# W640D.net
KiCad netlist of a schematic drawn in EAGLE
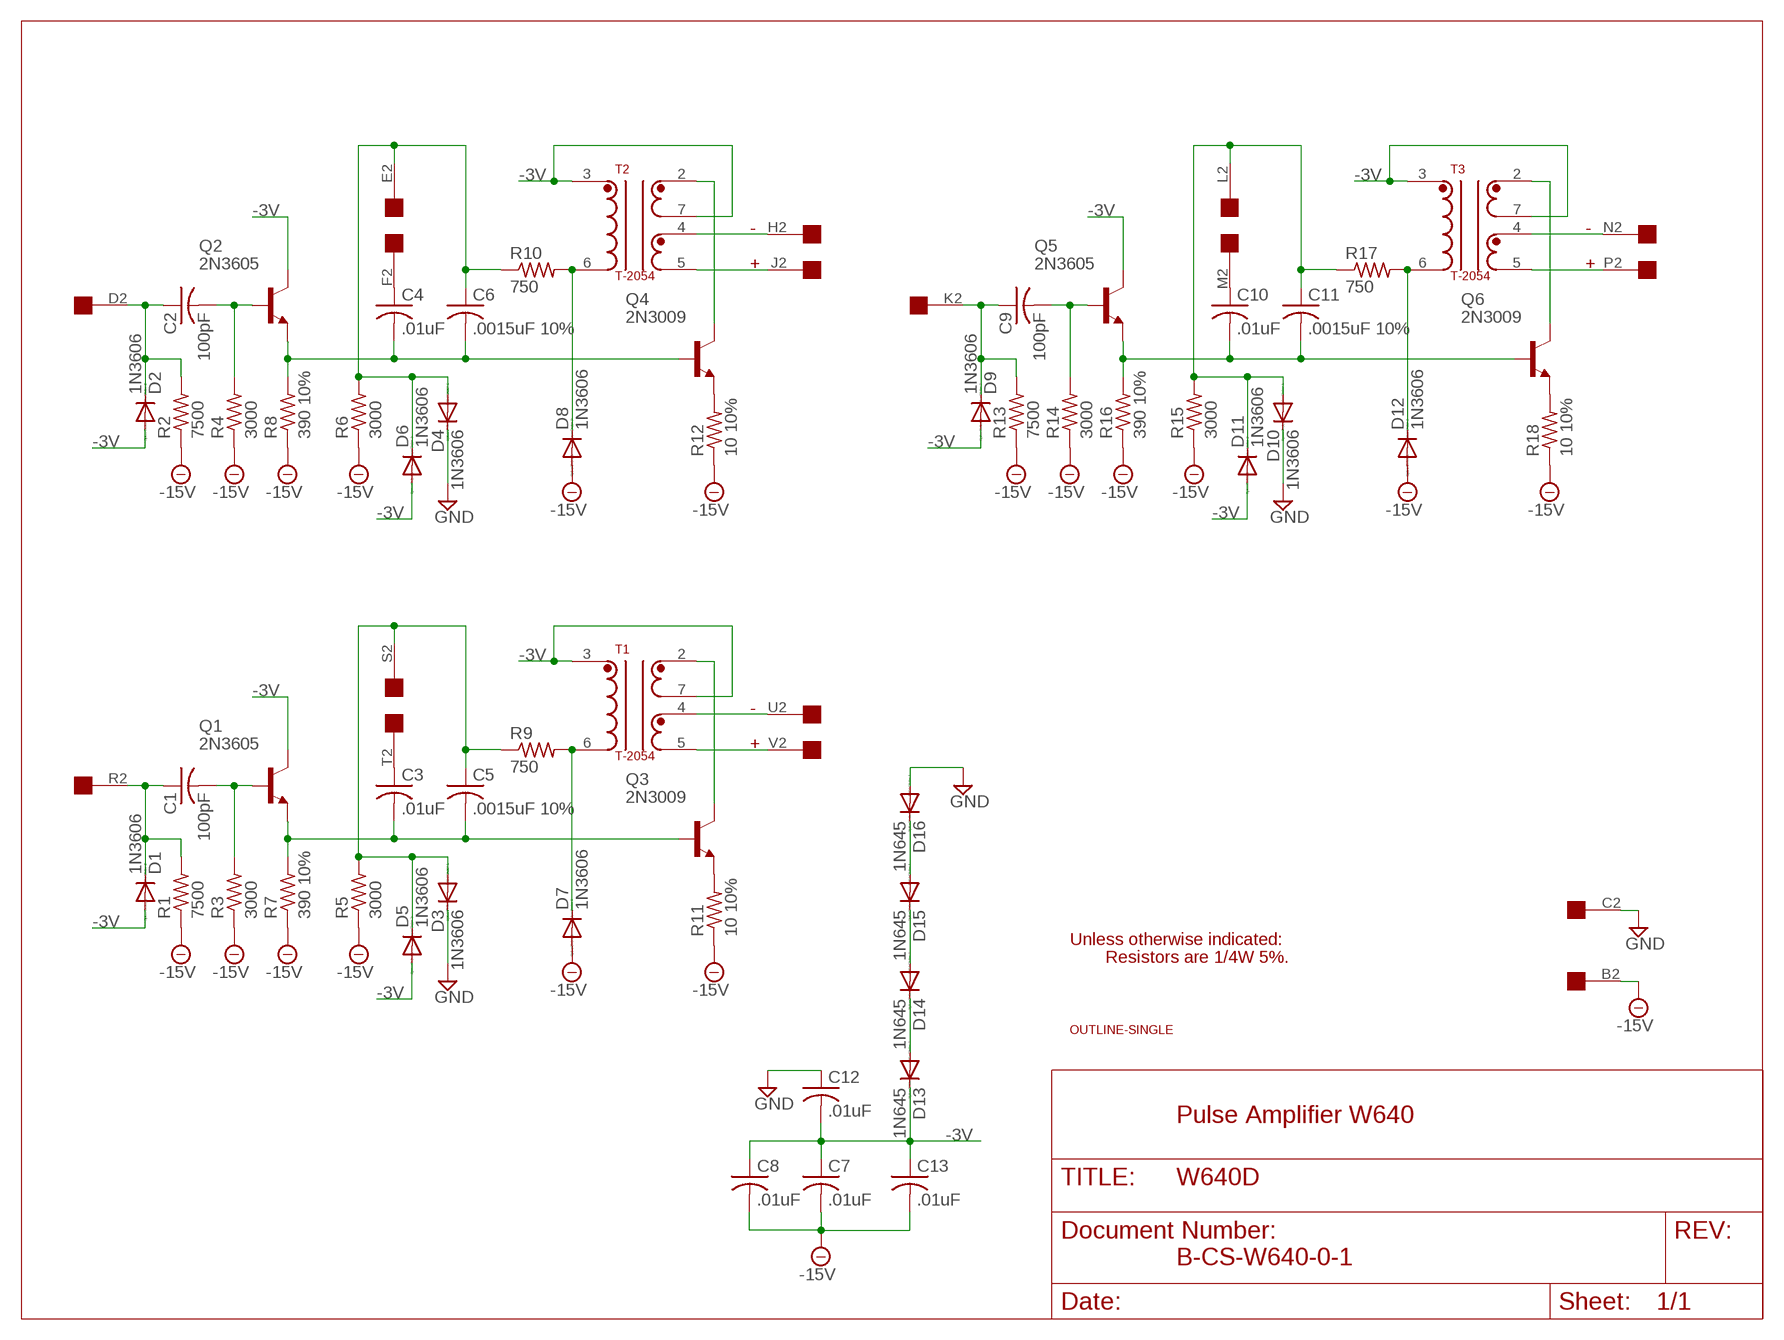
[diagram p0: schematic, sheet 1]

(export (version "E")
  (design (tool "Eeschema 10.0.6"))
  (components
    (comp (ref "C1")
      (value "100pF")
      (footprint "eagle-import:C050-025X075")
      (libsource (lib "eagle-import") (part "C-US050-025X075"))
    )
    (comp (ref "C2")
      (value "100pF")
      (footprint "eagle-import:C050-025X075")
      (libsource (lib "eagle-import") (part "C-US050-025X075"))
    )
    (comp (ref "C3")
      (value ".01uF")
      (footprint "eagle-import:C050-025X075")
      (libsource (lib "eagle-import") (part "C-US050-025X075"))
    )
    (comp (ref "C4")
      (value ".01uF")
      (footprint "eagle-import:C050-025X075")
      (libsource (lib "eagle-import") (part "C-US050-025X075"))
    )
    (comp (ref "C5")
      (value ".0015uF 10%")
      (footprint "eagle-import:C050-025X075")
      (libsource (lib "eagle-import") (part "C-US050-025X075"))
    )
    (comp (ref "C6")
      (value ".0015uF 10%")
      (footprint "eagle-import:C050-025X075")
      (libsource (lib "eagle-import") (part "C-US050-025X075"))
    )
    (comp (ref "C7")
      (value ".01uF")
      (footprint "eagle-import:C050-025X075")
      (libsource (lib "eagle-import") (part "C-US050-025X075"))
    )
    (comp (ref "C8")
      (value ".01uF")
      (footprint "eagle-import:C050-025X075")
      (libsource (lib "eagle-import") (part "C-US050-025X075"))
    )
    (comp (ref "C9")
      (value "100pF")
      (footprint "eagle-import:C050-025X075")
      (libsource (lib "eagle-import") (part "C-US050-025X075"))
    )
    (comp (ref "C10")
      (value ".01uF")
      (footprint "eagle-import:C050-025X075")
      (libsource (lib "eagle-import") (part "C-US050-025X075"))
    )
    (comp (ref "C11")
      (value ".0015uF 10%")
      (footprint "eagle-import:C050-025X075")
      (libsource (lib "eagle-import") (part "C-US050-025X075"))
    )
    (comp (ref "C12")
      (value ".01uF")
      (footprint "eagle-import:C050-025X075")
      (libsource (lib "eagle-import") (part "C-US050-025X075"))
    )
    (comp (ref "C13")
      (value ".01uF")
      (footprint "eagle-import:C050-025X075")
      (libsource (lib "eagle-import") (part "C-US050-025X075"))
    )
    (comp (ref "D1")
      (value "1N3606")
      (footprint "eagle-import:DO35-10")
      (libsource (lib "eagle-import") (part "1N4148DO35-10"))
    )
    (comp (ref "D2")
      (value "1N3606")
      (footprint "eagle-import:DO35-10")
      (libsource (lib "eagle-import") (part "1N4148DO35-10"))
    )
    (comp (ref "D3")
      (value "1N3606")
      (footprint "eagle-import:DO35-10")
      (libsource (lib "eagle-import") (part "1N4148DO35-10"))
    )
    (comp (ref "D4")
      (value "1N3606")
      (footprint "eagle-import:DO35-10")
      (libsource (lib "eagle-import") (part "1N4148DO35-10"))
    )
    (comp (ref "D5")
      (value "1N3606")
      (footprint "eagle-import:DO35-10")
      (libsource (lib "eagle-import") (part "1N4148DO35-10"))
    )
    (comp (ref "D6")
      (value "1N3606")
      (footprint "eagle-import:DO35-10")
      (libsource (lib "eagle-import") (part "1N4148DO35-10"))
    )
    (comp (ref "D7")
      (value "1N3606")
      (footprint "eagle-import:DO35-10")
      (libsource (lib "eagle-import") (part "1N4148DO35-10"))
    )
    (comp (ref "D8")
      (value "1N3606")
      (footprint "eagle-import:DO35-10")
      (libsource (lib "eagle-import") (part "1N4148DO35-10"))
    )
    (comp (ref "D9")
      (value "1N3606")
      (footprint "eagle-import:DO35-10")
      (libsource (lib "eagle-import") (part "1N4148DO35-10"))
    )
    (comp (ref "D10")
      (value "1N3606")
      (footprint "eagle-import:DO35-10")
      (libsource (lib "eagle-import") (part "1N4148DO35-10"))
    )
    (comp (ref "D11")
      (value "1N3606")
      (footprint "eagle-import:DO35-10")
      (libsource (lib "eagle-import") (part "1N4148DO35-10"))
    )
    (comp (ref "D12")
      (value "1N3606")
      (footprint "eagle-import:DO35-10")
      (libsource (lib "eagle-import") (part "1N4148DO35-10"))
    )
    (comp (ref "D13")
      (value "1N645")
      (footprint "eagle-import:DO35-10")
      (libsource (lib "eagle-import") (part "1N4148DO35-10"))
    )
    (comp (ref "D14")
      (value "1N645")
      (footprint "eagle-import:DO35-10")
      (libsource (lib "eagle-import") (part "1N4148DO35-10"))
    )
    (comp (ref "D15")
      (value "1N645")
      (footprint "eagle-import:DO35-10")
      (libsource (lib "eagle-import") (part "1N4148DO35-10"))
    )
    (comp (ref "D16")
      (value "1N645")
      (footprint "eagle-import:DO35-10")
      (libsource (lib "eagle-import") (part "1N4148DO35-10"))
    )
    (comp (ref "Q1")
      (value "2N3605")
      (footprint "eagle-import:TO5")
      (libsource (lib "eagle-import") (part "2N2219"))
    )
    (comp (ref "Q2")
      (value "2N3605")
      (footprint "eagle-import:TO5")
      (libsource (lib "eagle-import") (part "2N2219"))
    )
    (comp (ref "Q3")
      (value "2N3009")
      (footprint "eagle-import:TO5")
      (libsource (lib "eagle-import") (part "2N2219"))
    )
    (comp (ref "Q4")
      (value "2N3009")
      (footprint "eagle-import:TO5")
      (libsource (lib "eagle-import") (part "2N2219"))
    )
    (comp (ref "Q5")
      (value "2N3605")
      (footprint "eagle-import:TO5")
      (libsource (lib "eagle-import") (part "2N2219"))
    )
    (comp (ref "Q6")
      (value "2N3009")
      (footprint "eagle-import:TO5")
      (libsource (lib "eagle-import") (part "2N2219"))
    )
    (comp (ref "R1")
      (value "7500")
      (footprint "eagle-import:0207_10")
      (libsource (lib "eagle-import") (part "R-US_0207/10"))
    )
    (comp (ref "R2")
      (value "7500")
      (footprint "eagle-import:0207_10")
      (libsource (lib "eagle-import") (part "R-US_0207/10"))
    )
    (comp (ref "R3")
      (value "3000")
      (footprint "eagle-import:0207_10")
      (libsource (lib "eagle-import") (part "R-US_0207/10"))
    )
    (comp (ref "R4")
      (value "3000")
      (footprint "eagle-import:0207_10")
      (libsource (lib "eagle-import") (part "R-US_0207/10"))
    )
    (comp (ref "R5")
      (value "3000")
      (footprint "eagle-import:0207_10")
      (libsource (lib "eagle-import") (part "R-US_0207/10"))
    )
    (comp (ref "R6")
      (value "3000")
      (footprint "eagle-import:0207_10")
      (libsource (lib "eagle-import") (part "R-US_0207/10"))
    )
    (comp (ref "R7")
      (value "390 10%")
      (footprint "eagle-import:0207_10")
      (libsource (lib "eagle-import") (part "R-US_0207/10"))
    )
    (comp (ref "R8")
      (value "390 10%")
      (footprint "eagle-import:0207_10")
      (libsource (lib "eagle-import") (part "R-US_0207/10"))
    )
    (comp (ref "R9")
      (value "750")
      (footprint "eagle-import:0207_10")
      (libsource (lib "eagle-import") (part "R-US_0207/10"))
    )
    (comp (ref "R10")
      (value "750")
      (footprint "eagle-import:0207_10")
      (libsource (lib "eagle-import") (part "R-US_0207/10"))
    )
    (comp (ref "R11")
      (value "10 10%")
      (footprint "eagle-import:0207_10")
      (libsource (lib "eagle-import") (part "R-US_0207/10"))
    )
    (comp (ref "R12")
      (value "10 10%")
      (footprint "eagle-import:0207_10")
      (libsource (lib "eagle-import") (part "R-US_0207/10"))
    )
    (comp (ref "R13")
      (value "7500")
      (footprint "eagle-import:0207_10")
      (libsource (lib "eagle-import") (part "R-US_0207/10"))
    )
    (comp (ref "R14")
      (value "3000")
      (footprint "eagle-import:0207_10")
      (libsource (lib "eagle-import") (part "R-US_0207/10"))
    )
    (comp (ref "R15")
      (value "3000")
      (footprint "eagle-import:0207_10")
      (libsource (lib "eagle-import") (part "R-US_0207/10"))
    )
    (comp (ref "R16")
      (value "390 10%")
      (footprint "eagle-import:0207_10")
      (libsource (lib "eagle-import") (part "R-US_0207/10"))
    )
    (comp (ref "R17")
      (value "750")
      (footprint "eagle-import:0207_10")
      (libsource (lib "eagle-import") (part "R-US_0207/10"))
    )
    (comp (ref "R18")
      (value "10 10%")
      (footprint "eagle-import:0207_10")
      (libsource (lib "eagle-import") (part "R-US_0207/10"))
    )
    (comp (ref "T1")
      (value "T-2054")
      (footprint "eagle-import:TRANSFORMER6B")
      (libsource (lib "eagle-import") (part "T-2054"))
    )
    (comp (ref "T2")
      (value "T-2054")
      (footprint "eagle-import:TRANSFORMER6B")
      (libsource (lib "eagle-import") (part "T-2054"))
    )
    (comp (ref "T3")
      (value "T-2054")
      (footprint "eagle-import:TRANSFORMER6B")
      (libsource (lib "eagle-import") (part "T-2054"))
    )
    (comp (ref "U$1")
      (value "OUTLINE-SINGLE")
      (footprint "eagle-import:SINGLE")
      (libsource (lib "eagle-import") (part "OUTLINE-SINGLE"))
    )
    (comp (ref "U$2")
      (value "EDGE-1")
      (footprint "eagle-import:EDGE-CON1")
      (libsource (lib "eagle-import") (part "EDGE-1"))
    )
  )
  (nets
    (net (code "1") (name "-15V") (class "Default")
      (node (ref "C13") (pin "2") (pinfunction "2_2") (pintype "passive"))
      (node (ref "C7") (pin "2") (pinfunction "2_2") (pintype "passive"))
      (node (ref "C8") (pin "2") (pinfunction "2_2") (pintype "passive"))
      (node (ref "D12") (pin "A") (pinfunction "A_A") (pintype "passive"))
      (node (ref "D7") (pin "A") (pinfunction "A_A") (pintype "passive"))
      (node (ref "D8") (pin "A") (pinfunction "A_A") (pintype "passive"))
      (node (ref "R1") (pin "1") (pinfunction "1_1") (pintype "passive"))
      (node (ref "R11") (pin "1") (pinfunction "1_1") (pintype "passive"))
      (node (ref "R12") (pin "1") (pinfunction "1_1") (pintype "passive"))
      (node (ref "R13") (pin "1") (pinfunction "1_1") (pintype "passive"))
      (node (ref "R14") (pin "1") (pinfunction "1_1") (pintype "passive"))
      (node (ref "R15") (pin "1") (pinfunction "1_1") (pintype "passive"))
      (node (ref "R16") (pin "1") (pinfunction "1_1") (pintype "passive"))
      (node (ref "R18") (pin "1") (pinfunction "1_1") (pintype "passive"))
      (node (ref "R2") (pin "1") (pinfunction "1_1") (pintype "passive"))
      (node (ref "R3") (pin "1") (pinfunction "1_1") (pintype "passive"))
      (node (ref "R4") (pin "1") (pinfunction "1_1") (pintype "passive"))
      (node (ref "R5") (pin "1") (pinfunction "1_1") (pintype "passive"))
      (node (ref "R6") (pin "1") (pinfunction "1_1") (pintype "passive"))
      (node (ref "R7") (pin "1") (pinfunction "1_1") (pintype "passive"))
      (node (ref "R8") (pin "1") (pinfunction "1_1") (pintype "passive"))
      (node (ref "U$2") (pin "B2") (pinfunction "1_B2") (pintype "bidirectional"))
    )
    (net (code "2") (name "/-3V") (class "Default")
      (node (ref "C12") (pin "2") (pinfunction "2_2") (pintype "passive"))
      (node (ref "C13") (pin "1") (pinfunction "1_1") (pintype "passive"))
      (node (ref "C7") (pin "1") (pinfunction "1_1") (pintype "passive"))
      (node (ref "C8") (pin "1") (pinfunction "1_1") (pintype "passive"))
      (node (ref "D1") (pin "A") (pinfunction "A_A") (pintype "passive"))
      (node (ref "D11") (pin "A") (pinfunction "A_A") (pintype "passive"))
      (node (ref "D13") (pin "C") (pinfunction "C_C") (pintype "passive"))
      (node (ref "D2") (pin "A") (pinfunction "A_A") (pintype "passive"))
      (node (ref "D5") (pin "A") (pinfunction "A_A") (pintype "passive"))
      (node (ref "D6") (pin "A") (pinfunction "A_A") (pintype "passive"))
      (node (ref "D9") (pin "A") (pinfunction "A_A") (pintype "passive"))
      (node (ref "Q1") (pin "3") (pinfunction "C_3") (pintype "passive"))
      (node (ref "Q2") (pin "3") (pinfunction "C_3") (pintype "passive"))
      (node (ref "Q5") (pin "3") (pinfunction "C_3") (pintype "passive"))
      (node (ref "T1") (pin "3") (pinfunction "3_3") (pintype "passive"))
      (node (ref "T1") (pin "7") (pinfunction "5_7") (pintype "passive"))
      (node (ref "T2") (pin "3") (pinfunction "3_3") (pintype "passive"))
      (node (ref "T2") (pin "7") (pinfunction "5_7") (pintype "passive"))
      (node (ref "T3") (pin "3") (pinfunction "3_3") (pintype "passive"))
      (node (ref "T3") (pin "7") (pinfunction "5_7") (pintype "passive"))
    )
    (net (code "3") (name "GND") (class "Default")
      (node (ref "C12") (pin "1") (pinfunction "1_1") (pintype "passive"))
      (node (ref "D10") (pin "C") (pinfunction "C_C") (pintype "passive"))
      (node (ref "D16") (pin "A") (pinfunction "A_A") (pintype "passive"))
      (node (ref "D3") (pin "C") (pinfunction "C_C") (pintype "passive"))
      (node (ref "D4") (pin "C") (pinfunction "C_C") (pintype "passive"))
      (node (ref "U$2") (pin "C2") (pinfunction "1_C2") (pintype "bidirectional"))
    )
    (net (code "4") (name "Net-(D13-PadA)") (class "Default")
      (node (ref "D13") (pin "A") (pinfunction "A_A") (pintype "passive"))
      (node (ref "D14") (pin "C") (pinfunction "C_C") (pintype "passive"))
    )
    (net (code "5") (name "Net-(D14-PadA)") (class "Default")
      (node (ref "D14") (pin "A") (pinfunction "A_A") (pintype "passive"))
      (node (ref "D15") (pin "C") (pinfunction "C_C") (pintype "passive"))
    )
    (net (code "6") (name "Net-(D15-PadA)") (class "Default")
      (node (ref "D15") (pin "A") (pinfunction "A_A") (pintype "passive"))
      (node (ref "D16") (pin "C") (pinfunction "C_C") (pintype "passive"))
    )
    (net (code "7") (name "Net-(Q1-B)") (class "Default")
      (node (ref "C1") (pin "2") (pinfunction "2_2") (pintype "passive"))
      (node (ref "Q1") (pin "2") (pinfunction "B_2") (pintype "passive"))
      (node (ref "R3") (pin "2") (pinfunction "2_2") (pintype "passive"))
    )
    (net (code "8") (name "Net-(Q1-E)") (class "Default")
      (node (ref "C3") (pin "2") (pinfunction "2_2") (pintype "passive"))
      (node (ref "C5") (pin "2") (pinfunction "2_2") (pintype "passive"))
      (node (ref "Q1") (pin "1") (pinfunction "E_1") (pintype "passive"))
      (node (ref "Q3") (pin "2") (pinfunction "B_2") (pintype "passive"))
      (node (ref "R7") (pin "2") (pinfunction "2_2") (pintype "passive"))
    )
    (net (code "9") (name "Net-(Q2-B)") (class "Default")
      (node (ref "C2") (pin "2") (pinfunction "2_2") (pintype "passive"))
      (node (ref "Q2") (pin "2") (pinfunction "B_2") (pintype "passive"))
      (node (ref "R4") (pin "2") (pinfunction "2_2") (pintype "passive"))
    )
    (net (code "10") (name "Net-(Q2-E)") (class "Default")
      (node (ref "C4") (pin "2") (pinfunction "2_2") (pintype "passive"))
      (node (ref "C6") (pin "2") (pinfunction "2_2") (pintype "passive"))
      (node (ref "Q2") (pin "1") (pinfunction "E_1") (pintype "passive"))
      (node (ref "Q4") (pin "2") (pinfunction "B_2") (pintype "passive"))
      (node (ref "R8") (pin "2") (pinfunction "2_2") (pintype "passive"))
    )
    (net (code "11") (name "Net-(Q3-C)") (class "Default")
      (node (ref "Q3") (pin "3") (pinfunction "C_3") (pintype "passive"))
      (node (ref "T1") (pin "2") (pinfunction "2_2") (pintype "passive"))
    )
    (net (code "12") (name "Net-(Q3-E)") (class "Default")
      (node (ref "Q3") (pin "1") (pinfunction "E_1") (pintype "passive"))
      (node (ref "R11") (pin "2") (pinfunction "2_2") (pintype "passive"))
    )
    (net (code "13") (name "Net-(Q4-C)") (class "Default")
      (node (ref "Q4") (pin "3") (pinfunction "C_3") (pintype "passive"))
      (node (ref "T2") (pin "2") (pinfunction "2_2") (pintype "passive"))
    )
    (net (code "14") (name "Net-(Q4-E)") (class "Default")
      (node (ref "Q4") (pin "1") (pinfunction "E_1") (pintype "passive"))
      (node (ref "R12") (pin "2") (pinfunction "2_2") (pintype "passive"))
    )
    (net (code "15") (name "Net-(Q5-B)") (class "Default")
      (node (ref "C9") (pin "2") (pinfunction "2_2") (pintype "passive"))
      (node (ref "Q5") (pin "2") (pinfunction "B_2") (pintype "passive"))
      (node (ref "R14") (pin "2") (pinfunction "2_2") (pintype "passive"))
    )
    (net (code "16") (name "Net-(Q5-E)") (class "Default")
      (node (ref "C10") (pin "2") (pinfunction "2_2") (pintype "passive"))
      (node (ref "C11") (pin "2") (pinfunction "2_2") (pintype "passive"))
      (node (ref "Q5") (pin "1") (pinfunction "E_1") (pintype "passive"))
      (node (ref "Q6") (pin "2") (pinfunction "B_2") (pintype "passive"))
      (node (ref "R16") (pin "2") (pinfunction "2_2") (pintype "passive"))
    )
    (net (code "17") (name "Net-(Q6-C)") (class "Default")
      (node (ref "Q6") (pin "3") (pinfunction "C_3") (pintype "passive"))
      (node (ref "T3") (pin "2") (pinfunction "2_2") (pintype "passive"))
    )
    (net (code "18") (name "Net-(Q6-E)") (class "Default")
      (node (ref "Q6") (pin "1") (pinfunction "E_1") (pintype "passive"))
      (node (ref "R18") (pin "2") (pinfunction "2_2") (pintype "passive"))
    )
    (net (code "19") (name "Net-(T1-1)") (class "Default")
      (node (ref "T1") (pin "4") (pinfunction "1_4") (pintype "passive"))
      (node (ref "U$2") (pin "U2") (pinfunction "1_U2") (pintype "bidirectional"))
    )
    (net (code "20") (name "Net-(T1-4)") (class "Default")
      (node (ref "D7") (pin "C") (pinfunction "C_C") (pintype "passive"))
      (node (ref "R9") (pin "2") (pinfunction "2_2") (pintype "passive"))
      (node (ref "T1") (pin "6") (pinfunction "4_6") (pintype "passive"))
    )
    (net (code "21") (name "Net-(T1-6)") (class "Default")
      (node (ref "T1") (pin "5") (pinfunction "6_5") (pintype "passive"))
      (node (ref "U$2") (pin "V2") (pinfunction "1_V2") (pintype "bidirectional"))
    )
    (net (code "22") (name "Net-(T2-1)") (class "Default")
      (node (ref "T2") (pin "4") (pinfunction "1_4") (pintype "passive"))
      (node (ref "U$2") (pin "H2") (pinfunction "1_H2") (pintype "bidirectional"))
    )
    (net (code "23") (name "Net-(T2-4)") (class "Default")
      (node (ref "D8") (pin "C") (pinfunction "C_C") (pintype "passive"))
      (node (ref "R10") (pin "2") (pinfunction "2_2") (pintype "passive"))
      (node (ref "T2") (pin "6") (pinfunction "4_6") (pintype "passive"))
    )
    (net (code "24") (name "Net-(T2-6)") (class "Default")
      (node (ref "T2") (pin "5") (pinfunction "6_5") (pintype "passive"))
      (node (ref "U$2") (pin "J2") (pinfunction "1_J2") (pintype "bidirectional"))
    )
    (net (code "25") (name "Net-(T3-1)") (class "Default")
      (node (ref "T3") (pin "4") (pinfunction "1_4") (pintype "passive"))
      (node (ref "U$2") (pin "N2") (pinfunction "1_N2") (pintype "bidirectional"))
    )
    (net (code "26") (name "Net-(T3-4)") (class "Default")
      (node (ref "D12") (pin "C") (pinfunction "C_C") (pintype "passive"))
      (node (ref "R17") (pin "2") (pinfunction "2_2") (pintype "passive"))
      (node (ref "T3") (pin "6") (pinfunction "4_6") (pintype "passive"))
    )
    (net (code "27") (name "Net-(T3-6)") (class "Default")
      (node (ref "T3") (pin "5") (pinfunction "6_5") (pintype "passive"))
      (node (ref "U$2") (pin "P2") (pinfunction "1_P2") (pintype "bidirectional"))
    )
    (net (code "28") (name "Net-(U$2D-1)") (class "Default")
      (node (ref "C2") (pin "1") (pinfunction "1_1") (pintype "passive"))
      (node (ref "D2") (pin "C") (pinfunction "C_C") (pintype "passive"))
      (node (ref "R2") (pin "2") (pinfunction "2_2") (pintype "passive"))
      (node (ref "U$2") (pin "D2") (pinfunction "1_D2") (pintype "bidirectional"))
    )
    (net (code "29") (name "Net-(U$2E-1)") (class "Default")
      (node (ref "C6") (pin "1") (pinfunction "1_1") (pintype "passive"))
      (node (ref "D4") (pin "A") (pinfunction "A_A") (pintype "passive"))
      (node (ref "D6") (pin "C") (pinfunction "C_C") (pintype "passive"))
      (node (ref "R10") (pin "1") (pinfunction "1_1") (pintype "passive"))
      (node (ref "R6") (pin "2") (pinfunction "2_2") (pintype "passive"))
      (node (ref "U$2") (pin "E2") (pinfunction "1_E2") (pintype "bidirectional"))
    )
    (net (code "30") (name "Net-(U$2F-1)") (class "Default")
      (node (ref "C4") (pin "1") (pinfunction "1_1") (pintype "passive"))
      (node (ref "U$2") (pin "F2") (pinfunction "1_F2") (pintype "bidirectional"))
    )
    (net (code "31") (name "Net-(U$2I-1)") (class "Default")
      (node (ref "C9") (pin "1") (pinfunction "1_1") (pintype "passive"))
      (node (ref "D9") (pin "C") (pinfunction "C_C") (pintype "passive"))
      (node (ref "R13") (pin "2") (pinfunction "2_2") (pintype "passive"))
      (node (ref "U$2") (pin "K2") (pinfunction "1_K2") (pintype "bidirectional"))
    )
    (net (code "32") (name "Net-(U$2J-1)") (class "Default")
      (node (ref "C11") (pin "1") (pinfunction "1_1") (pintype "passive"))
      (node (ref "D10") (pin "A") (pinfunction "A_A") (pintype "passive"))
      (node (ref "D11") (pin "C") (pinfunction "C_C") (pintype "passive"))
      (node (ref "R15") (pin "2") (pinfunction "2_2") (pintype "passive"))
      (node (ref "R17") (pin "1") (pinfunction "1_1") (pintype "passive"))
      (node (ref "U$2") (pin "L2") (pinfunction "1_L2") (pintype "bidirectional"))
    )
    (net (code "33") (name "Net-(U$2K-1)") (class "Default")
      (node (ref "C10") (pin "1") (pinfunction "1_1") (pintype "passive"))
      (node (ref "U$2") (pin "M2") (pinfunction "1_M2") (pintype "bidirectional"))
    )
    (net (code "34") (name "Net-(U$2N-1)") (class "Default")
      (node (ref "C1") (pin "1") (pinfunction "1_1") (pintype "passive"))
      (node (ref "D1") (pin "C") (pinfunction "C_C") (pintype "passive"))
      (node (ref "R1") (pin "2") (pinfunction "2_2") (pintype "passive"))
      (node (ref "U$2") (pin "R2") (pinfunction "1_R2") (pintype "bidirectional"))
    )
    (net (code "35") (name "Net-(U$2O-1)") (class "Default")
      (node (ref "C5") (pin "1") (pinfunction "1_1") (pintype "passive"))
      (node (ref "D3") (pin "A") (pinfunction "A_A") (pintype "passive"))
      (node (ref "D5") (pin "C") (pinfunction "C_C") (pintype "passive"))
      (node (ref "R5") (pin "2") (pinfunction "2_2") (pintype "passive"))
      (node (ref "R9") (pin "1") (pinfunction "1_1") (pintype "passive"))
      (node (ref "U$2") (pin "S2") (pinfunction "1_S2") (pintype "bidirectional"))
    )
    (net (code "36") (name "Net-(U$2P-1)") (class "Default")
      (node (ref "C3") (pin "1") (pinfunction "1_1") (pintype "passive"))
      (node (ref "U$2") (pin "T2") (pinfunction "1_T2") (pintype "bidirectional"))
    )
  )
)
